# Sheet1.net
KiCad netlist of a schematic drawn in Altium Designer
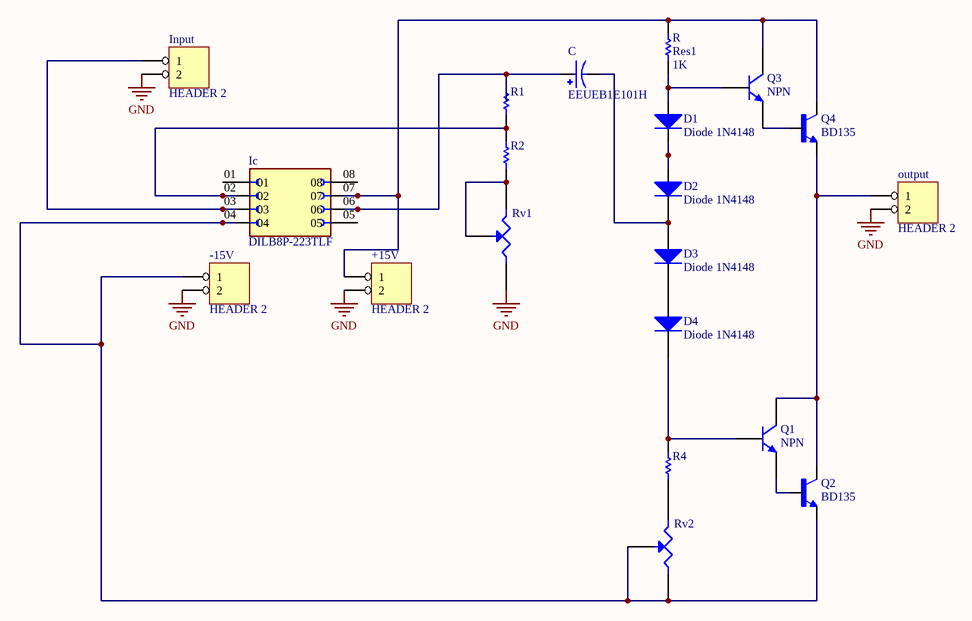
[diagram p0: Sheet1.SchDoc]

(export (version "E")
  (design (tool "Eeschema 10.0.6"))
  (components
    (comp (ref "+15V")
      (value "HEADER 2")
      (footprint "RAD0.2")
      (libsource (lib "Library (1)") (part "HEADER 2"))
    )
    (comp (ref "-15V")
      (value "HEADER 2")
      (footprint "RAD0.2")
      (libsource (lib "Library (1)") (part "HEADER 2"))
    )
    (comp (ref "C")
      (value "EEUEB1E101H")
      (footprint "CAPPRD250W50D630H1500")
      (description "CAP ALUM 100UF 20% 25V RADIAL")
      (fields (field (name "MP") "EEU-EB1E101H") (field (name "MF") "Panasonic Electronic Components"))
      (libsource (lib "EEUEB1E101H") (part "EEUEB1E101H"))
    )
    (comp (ref "D1")
      (value "Diode 1N4148")
      (footprint "DO-35")
      (description "High Conductance Fast Diode")
      (fields (field (name "PUBLISHER") "Altium Limited"))
      (libsource (lib "Miscellaneous Devices") (part "Diode 1N4148"))
    )
    (comp (ref "D2")
      (value "Diode 1N4148")
      (footprint "DO-35")
      (description "High Conductance Fast Diode")
      (fields (field (name "PUBLISHER") "Altium Limited"))
      (libsource (lib "Miscellaneous Devices") (part "Diode 1N4148"))
    )
    (comp (ref "D3")
      (value "Diode 1N4148")
      (footprint "DO-35")
      (description "High Conductance Fast Diode")
      (fields (field (name "PUBLISHER") "Altium Limited"))
      (libsource (lib "Miscellaneous Devices") (part "Diode 1N4148"))
    )
    (comp (ref "D4")
      (value "Diode 1N4148")
      (footprint "DO-35")
      (description "High Conductance Fast Diode")
      (fields (field (name "PUBLISHER") "Altium Limited"))
      (libsource (lib "Miscellaneous Devices") (part "Diode 1N4148"))
    )
    (comp (ref "Ic")
      (value "DILB8P-223TLF")
      (footprint "AMPHENOL_DILB8P-223TLF")
      (description "DIP Socket, Stamped and Formed")
      (fields (field (name "MF") "Amphenol ICC"))
      (libsource (lib "DILB8P-223TLF") (part "DILB8P-223TLF"))
    )
    (comp (ref "Input")
      (value "HEADER 2")
      (footprint "RAD0.2")
      (libsource (lib "Library (1)") (part "HEADER 2"))
    )
    (comp (ref "output")
      (value "HEADER 2")
      (footprint "RAD0.2")
      (libsource (lib "Library (1)") (part "HEADER 2"))
    )
    (comp (ref "Q1")
      (value "NPN")
      (footprint "TO-226-AA")
      (description "NPN Bipolar Transistor")
      (fields (field (name "PUBLISHER") "Altium Limited"))
      (libsource (lib "Miscellaneous Devices") (part "NPN"))
    )
    (comp (ref "Q2")
      (value "BD135")
      (footprint "TO229P780X300X2000-3")
      (fields (field (name "MF") "ON Semiconductor"))
      (libsource (lib "BD135") (part "BD135"))
    )
    (comp (ref "Q3")
      (value "NPN")
      (footprint "TO-226-AA")
      (description "NPN Bipolar Transistor")
      (fields (field (name "PUBLISHER") "Altium Limited"))
      (libsource (lib "Miscellaneous Devices") (part "NPN"))
    )
    (comp (ref "Q4")
      (value "BD135")
      (footprint "TO229P780X300X2000-3")
      (fields (field (name "MF") "ON Semiconductor"))
      (libsource (lib "BD135") (part "BD135"))
    )
    (comp (ref "R")
      (value "Res1")
      (footprint "AXIAL-0.3")
      (description "Resistor")
      (fields (field (name "ALTIUM_VALUE") "1K") (field (name "PUBLISHER") "Altium Limited"))
      (libsource (lib "Miscellaneous Devices") (part "Res1"))
    )
    (comp (ref "R1")
      (value "~")
      (footprint "AXIAL-0.3")
      (description "Resistor")
      (fields (field (name "PUBLISHER") "Altium Limited"))
      (libsource (lib "Miscellaneous Devices") (part "Res1"))
    )
    (comp (ref "R2")
      (value "~")
      (footprint "AXIAL-0.3")
      (description "Resistor")
      (fields (field (name "PUBLISHER") "Altium Limited"))
      (libsource (lib "Miscellaneous Devices") (part "Res1"))
    )
    (comp (ref "R4")
      (value "~")
      (footprint "AXIAL-0.3")
      (description "Resistor")
      (fields (field (name "PUBLISHER") "Altium Limited"))
      (libsource (lib "Miscellaneous Devices") (part "Res1"))
    )
    (comp (ref "Rv1")
      (value "~")
      (footprint "POT")
      (description "Potentiometer")
      (libsource (lib "Library (1)") (part "POTENTIOMETER"))
    )
    (comp (ref "Rv2")
      (value "~")
      (footprint "POT")
      (description "Potentiometer")
      (libsource (lib "Library (1)") (part "POTENTIOMETER"))
    )
  )
  (nets
    (net (code "1") (name "GND") (class "Default")
      (node (ref "+15V") (pin "2") (pinfunction "2_2") (pintype "passive"))
      (node (ref "-15V") (pin "2") (pinfunction "2_2") (pintype "passive"))
      (node (ref "Input") (pin "2") (pinfunction "2_2") (pintype "passive"))
      (node (ref "Rv1") (pin "1") (pinfunction "1_1") (pintype "passive"))
      (node (ref "output") (pin "2") (pinfunction "2_2") (pintype "passive"))
    )
    (net (code "2") (name "Net-(C-PadP)") (class "Default")
      (node (ref "C") (pin "P") (pinfunction "P_P") (pintype "passive"))
      (node (ref "Ic") (pin "06") (pinfunction "06_06") (pintype "passive"))
      (node (ref "R1") (pin "2") (pinfunction "2_2") (pintype "passive"))
    )
    (net (code "3") (name "Net-(D1-A)") (class "Default")
      (node (ref "D1") (pin "1") (pinfunction "A_1") (pintype "passive"))
      (node (ref "Q3") (pin "2") (pinfunction "B_2") (pintype "passive"))
      (node (ref "R") (pin "1") (pinfunction "1_1") (pintype "passive"))
    )
    (net (code "4") (name "Net-(D1-K)") (class "Default")
      (node (ref "D1") (pin "2") (pinfunction "K_2") (pintype "passive"))
      (node (ref "D2") (pin "1") (pinfunction "A_1") (pintype "passive"))
    )
    (net (code "5") (name "Net-(D2-K)") (class "Default")
      (node (ref "C") (pin "N") (pinfunction "N_N") (pintype "passive"))
      (node (ref "D2") (pin "2") (pinfunction "K_2") (pintype "passive"))
      (node (ref "D3") (pin "1") (pinfunction "A_1") (pintype "passive"))
    )
    (net (code "6") (name "Net-(D3-K)") (class "Default")
      (node (ref "D3") (pin "2") (pinfunction "K_2") (pintype "passive"))
      (node (ref "D4") (pin "1") (pinfunction "A_1") (pintype "passive"))
    )
    (net (code "7") (name "Net-(D4-K)") (class "Default")
      (node (ref "D4") (pin "2") (pinfunction "K_2") (pintype "passive"))
      (node (ref "Q1") (pin "2") (pinfunction "B_2") (pintype "passive"))
      (node (ref "R4") (pin "2") (pinfunction "2_2") (pintype "passive"))
    )
    (net (code "8") (name "Net-(Ic-Pad02)") (class "Default")
      (node (ref "Ic") (pin "02") (pinfunction "02_02") (pintype "passive"))
      (node (ref "R1") (pin "1") (pinfunction "1_1") (pintype "passive"))
      (node (ref "R2") (pin "2") (pinfunction "2_2") (pintype "passive"))
    )
    (net (code "9") (name "Net-(Ic-Pad03)") (class "Default")
      (node (ref "Ic") (pin "03") (pinfunction "03_03") (pintype "passive"))
      (node (ref "Input") (pin "1") (pinfunction "1_1") (pintype "passive"))
    )
    (net (code "10") (name "Net-(Q1-C)") (class "Default")
      (node (ref "Q1") (pin "1") (pinfunction "C_1") (pintype "passive"))
      (node (ref "Q2") (pin "2") (pinfunction "C_2") (pintype "passive"))
      (node (ref "Q4") (pin "1") (pinfunction "E_1") (pintype "passive"))
      (node (ref "output") (pin "1") (pinfunction "1_1") (pintype "passive"))
    )
    (net (code "11") (name "Net-(Q1-E)") (class "Default")
      (node (ref "Q1") (pin "3") (pinfunction "E_3") (pintype "passive"))
      (node (ref "Q2") (pin "3") (pinfunction "B_3") (pintype "passive"))
    )
    (net (code "12") (name "Net-(Q2-E)") (class "Default")
      (node (ref "-15V") (pin "1") (pinfunction "1_1") (pintype "passive"))
      (node (ref "Ic") (pin "04") (pinfunction "04_04") (pintype "passive"))
      (node (ref "Q2") (pin "1") (pinfunction "E_1") (pintype "passive"))
      (node (ref "Rv2") (pin "1") (pinfunction "1_1") (pintype "passive"))
      (node (ref "Rv2") (pin "2") (pinfunction "2_2") (pintype "passive"))
    )
    (net (code "13") (name "Net-(Q3-C)") (class "Default")
      (node (ref "+15V") (pin "1") (pinfunction "1_1") (pintype "passive"))
      (node (ref "Ic") (pin "07") (pinfunction "07_07") (pintype "passive"))
      (node (ref "Q3") (pin "1") (pinfunction "C_1") (pintype "passive"))
      (node (ref "Q4") (pin "2") (pinfunction "C_2") (pintype "passive"))
      (node (ref "R") (pin "2") (pinfunction "2_2") (pintype "passive"))
    )
    (net (code "14") (name "Net-(Q3-E)") (class "Default")
      (node (ref "Q3") (pin "3") (pinfunction "E_3") (pintype "passive"))
      (node (ref "Q4") (pin "3") (pinfunction "B_3") (pintype "passive"))
    )
    (net (code "15") (name "Net-(R2-Pad1)") (class "Default")
      (node (ref "R2") (pin "1") (pinfunction "1_1") (pintype "passive"))
      (node (ref "Rv1") (pin "2") (pinfunction "2_2") (pintype "passive"))
      (node (ref "Rv1") (pin "3") (pinfunction "3_3") (pintype "passive"))
    )
    (net (code "16") (name "Net-(R4-Pad1)") (class "Default")
      (node (ref "R4") (pin "1") (pinfunction "1_1") (pintype "passive"))
      (node (ref "Rv2") (pin "3") (pinfunction "3_3") (pintype "passive"))
    )
    (net (code "17") (name "unconnected-(Ic-Pad01)") (class "Default")
      (node (ref "Ic") (pin "01") (pinfunction "01_01") (pintype "passive"))
    )
    (net (code "18") (name "unconnected-(Ic-Pad05)") (class "Default")
      (node (ref "Ic") (pin "05") (pinfunction "05_05") (pintype "passive"))
    )
    (net (code "19") (name "unconnected-(Ic-Pad08)") (class "Default")
      (node (ref "Ic") (pin "08") (pinfunction "08_08") (pintype "passive"))
    )
  )
)
